# Stepper_driver.net
KiCad netlist of a schematic drawn in Altium Designer
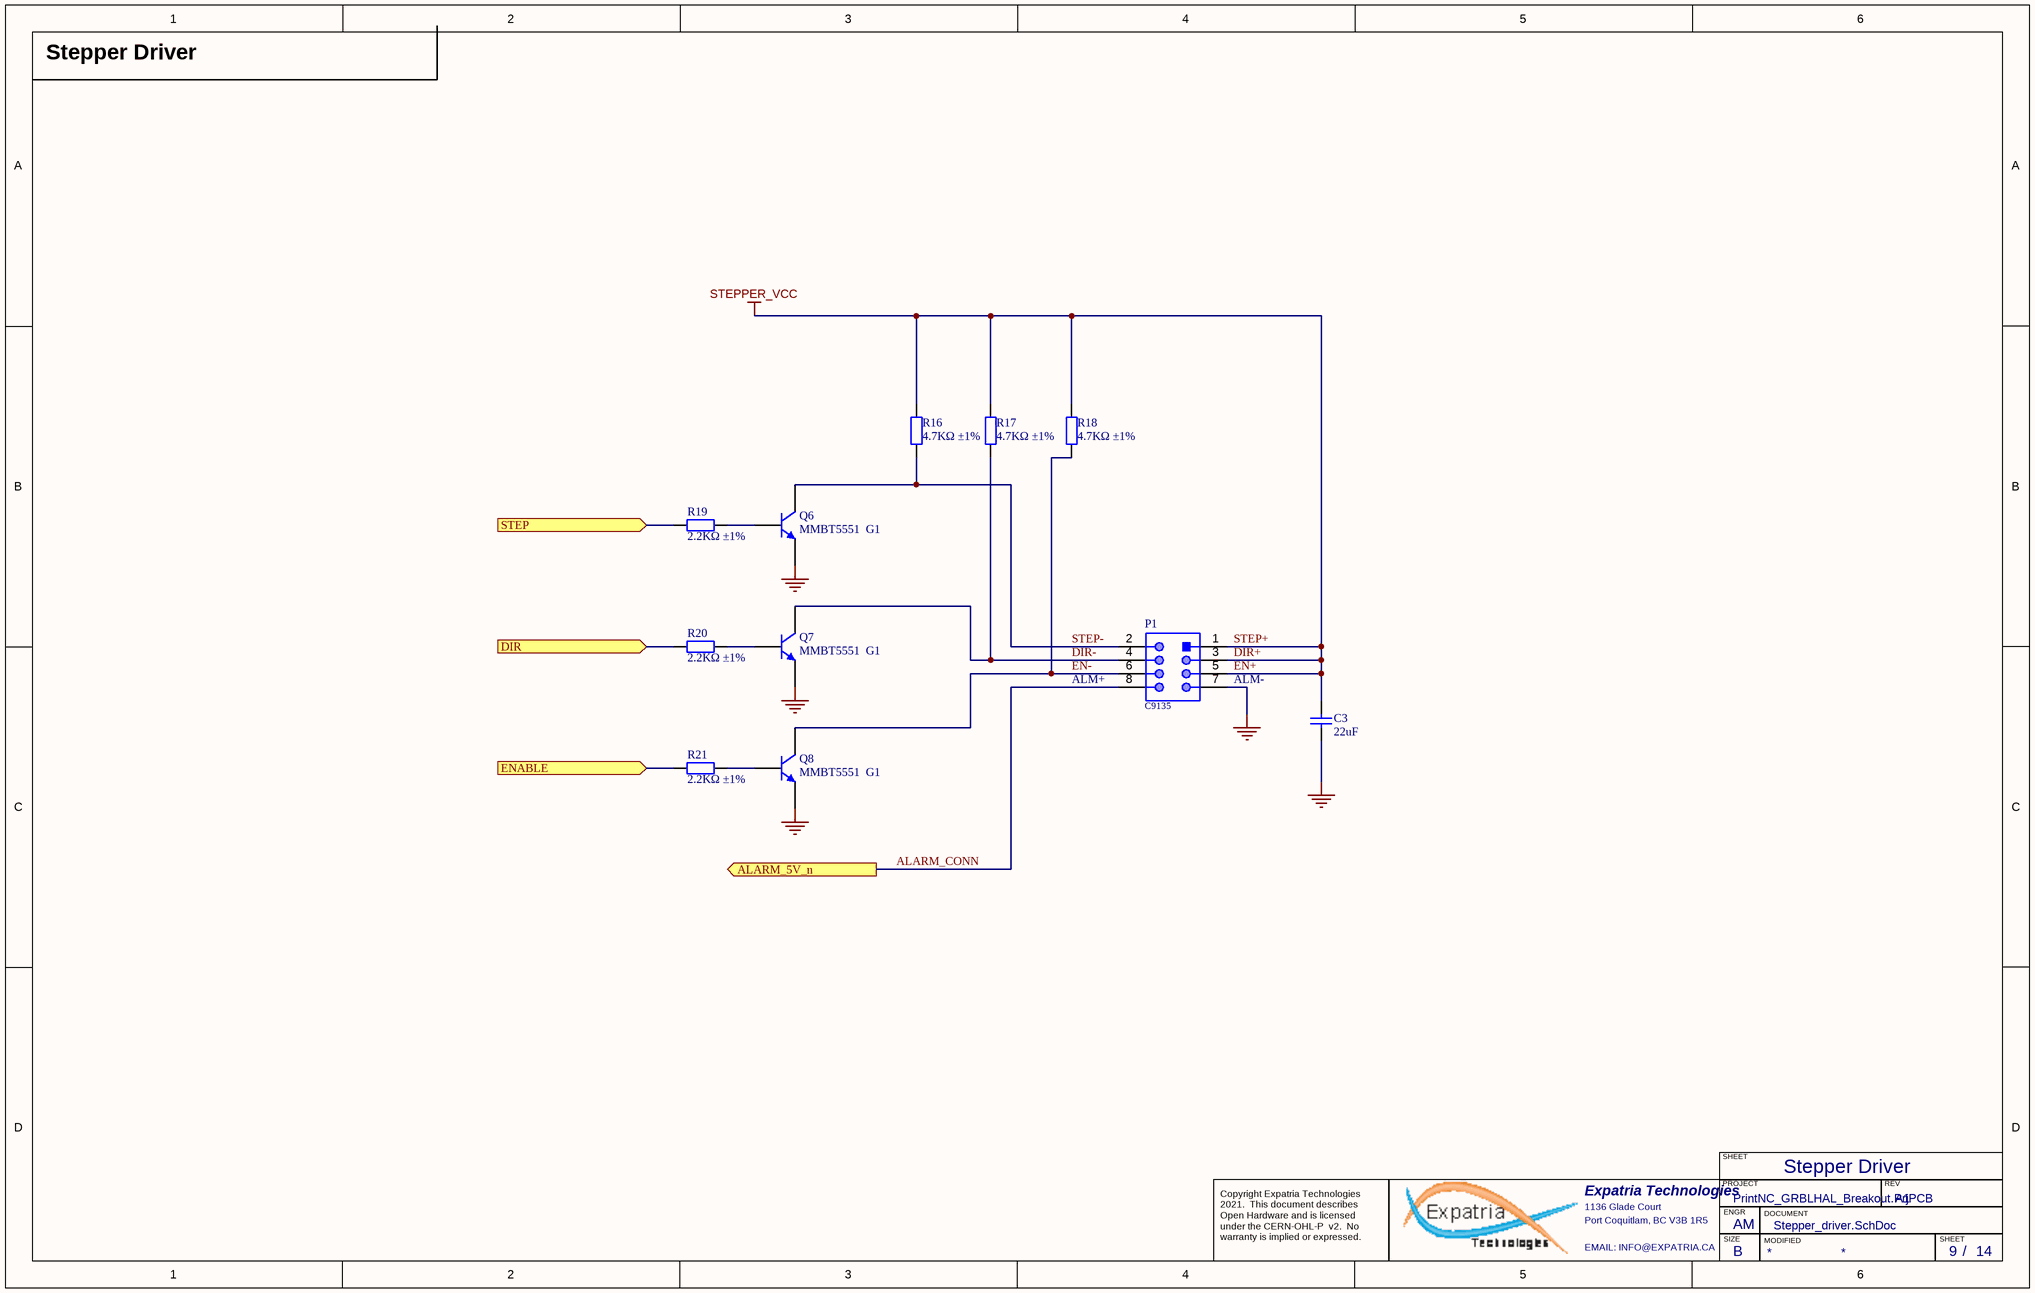
[diagram p0: Stepper_driver.SchDoc]

(export (version "E")
  (design (tool "Eeschema 10.0.6"))
  (components
    (comp (ref "C3")
      (value "22uF")
      (footprint "0805_C")
      (description "Chip capacitors")
      (fields
        (field (name "MANUFACTURER") "Samsung Electro-Mechanics")
        (field (name "PARTNUMBER") "CL21A226MAQNNNE")
      )
      (libsource (lib "Cap") (part "0805 22uF (226) 20% 25V"))
    )
    (comp (ref "P1")
      (value "C9135")
      (footprint "61200821621")
      (description "Male Box Header WR-BHD, THT, Vertical, pitch 2.54 mm, 8 pins")
      (fields (field (name "MANUFACTURER") "Wurth Elektronik") (field (name "PUBLISHER") "WurthElektronik"))
      (libsource (lib "PrintNC_GRBLHAL_Breakout") (part "WE-CN-2P-M-R8"))
    )
    (comp (ref "Q6")
      (value "MMBT5551  G1")
      (footprint "SOT-23(SOT-23-3)")
      (description "三极管")
      (libsource (lib "PrintNC_GRBLHAL_Breakout") (part "SOT-23 MMBT5551  G1"))
    )
    (comp (ref "Q7")
      (value "MMBT5551  G1")
      (footprint "SOT-23(SOT-23-3)")
      (description "三极管")
      (libsource (lib "PrintNC_GRBLHAL_Breakout") (part "SOT-23 MMBT5551  G1"))
    )
    (comp (ref "Q8")
      (value "MMBT5551  G1")
      (footprint "SOT-23(SOT-23-3)")
      (description "三极管")
      (libsource (lib "PrintNC_GRBLHAL_Breakout") (part "SOT-23 MMBT5551  G1"))
    )
    (comp (ref "R16")
      (value "4.7KΩ ±1%")
      (footprint "0402_R")
      (description "Chip resistor")
      (fields (field (name "MANUFACTURER") "Uniroyal Elec") (field (name "PARTNUMBER") "0402WGF4701TCE"))
      (libsource (lib "PrintNC_GRBLHAL_Breakout") (part "0402 4.7K (4701) 1%"))
    )
    (comp (ref "R17")
      (value "4.7KΩ ±1%")
      (footprint "0402_R")
      (description "Chip resistor")
      (fields (field (name "MANUFACTURER") "Uniroyal Elec") (field (name "PARTNUMBER") "0402WGF4701TCE"))
      (libsource (lib "PrintNC_GRBLHAL_Breakout") (part "0402 4.7K (4701) 1%"))
    )
    (comp (ref "R18")
      (value "4.7KΩ ±1%")
      (footprint "0402_R")
      (description "Chip resistor")
      (fields (field (name "MANUFACTURER") "Uniroyal Elec") (field (name "PARTNUMBER") "0402WGF4701TCE"))
      (libsource (lib "PrintNC_GRBLHAL_Breakout") (part "0402 4.7K (4701) 1%"))
    )
    (comp (ref "R19")
      (value "2.2KΩ ±1%")
      (footprint "0402_R")
      (description "Chip resistor")
      (fields (field (name "MANUFACTURER") "Uniroyal Elec") (field (name "PARTNUMBER") "0402WGF2201TCE"))
      (libsource (lib "PrintNC_GRBLHAL_Breakout") (part "0402 2.2K (2201) 1%"))
    )
    (comp (ref "R20")
      (value "2.2KΩ ±1%")
      (footprint "0402_R")
      (description "Chip resistor")
      (fields (field (name "MANUFACTURER") "Uniroyal Elec") (field (name "PARTNUMBER") "0402WGF2201TCE"))
      (libsource (lib "PrintNC_GRBLHAL_Breakout") (part "0402 2.2K (2201) 1%"))
    )
    (comp (ref "R21")
      (value "2.2KΩ ±1%")
      (footprint "0402_R")
      (description "Chip resistor")
      (fields (field (name "MANUFACTURER") "Uniroyal Elec") (field (name "PARTNUMBER") "0402WGF2201TCE"))
      (libsource (lib "PrintNC_GRBLHAL_Breakout") (part "0402 2.2K (2201) 1%"))
    )
  )
  (nets
    (net (code "1") (name "/ALARM_CONN") (class "Default")
      (node (ref "P1") (pin "8") (pinfunction "8_8") (pintype "passive"))
    )
    (net (code "2") (name "/DIR") (class "Default")
      (node (ref "R20") (pin "1") (pinfunction "1_1") (pintype "passive"))
    )
    (net (code "3") (name "/DIR-") (class "Default")
      (node (ref "P1") (pin "4") (pinfunction "4_4") (pintype "passive"))
      (node (ref "Q7") (pin "3") (pinfunction "C_3") (pintype "passive"))
      (node (ref "R17") (pin "1") (pinfunction "1_1") (pintype "passive"))
    )
    (net (code "4") (name "/EN-") (class "Default")
      (node (ref "P1") (pin "6") (pinfunction "6_6") (pintype "passive"))
      (node (ref "Q8") (pin "3") (pinfunction "C_3") (pintype "passive"))
      (node (ref "R18") (pin "1") (pinfunction "1_1") (pintype "passive"))
    )
    (net (code "5") (name "/ENABLE") (class "Default")
      (node (ref "R21") (pin "1") (pinfunction "1_1") (pintype "passive"))
    )
    (net (code "6") (name "/STEP") (class "Default")
      (node (ref "R19") (pin "1") (pinfunction "1_1") (pintype "passive"))
    )
    (net (code "7") (name "/STEP-") (class "Default")
      (node (ref "P1") (pin "2") (pinfunction "2_2") (pintype "passive"))
      (node (ref "Q6") (pin "3") (pinfunction "C_3") (pintype "passive"))
      (node (ref "R16") (pin "1") (pinfunction "1_1") (pintype "passive"))
    )
    (net (code "8") (name "GND") (class "Default")
      (node (ref "C3") (pin "1") (pinfunction "1_1") (pintype "passive"))
      (node (ref "P1") (pin "7") (pinfunction "7_7") (pintype "passive"))
      (node (ref "Q6") (pin "2") (pinfunction "E_2") (pintype "passive"))
      (node (ref "Q7") (pin "2") (pinfunction "E_2") (pintype "passive"))
      (node (ref "Q8") (pin "2") (pinfunction "E_2") (pintype "passive"))
    )
    (net (code "9") (name "Net-(Q6-B)") (class "Default")
      (node (ref "Q6") (pin "1") (pinfunction "B_1") (pintype "passive"))
      (node (ref "R19") (pin "2") (pinfunction "2_2") (pintype "passive"))
    )
    (net (code "10") (name "Net-(Q7-B)") (class "Default")
      (node (ref "Q7") (pin "1") (pinfunction "B_1") (pintype "passive"))
      (node (ref "R20") (pin "2") (pinfunction "2_2") (pintype "passive"))
    )
    (net (code "11") (name "Net-(Q8-B)") (class "Default")
      (node (ref "Q8") (pin "1") (pinfunction "B_1") (pintype "passive"))
      (node (ref "R21") (pin "2") (pinfunction "2_2") (pintype "passive"))
    )
    (net (code "12") (name "STEPPER_VCC") (class "Default")
      (node (ref "C3") (pin "2") (pinfunction "2_2") (pintype "passive"))
      (node (ref "P1") (pin "1") (pinfunction "1_1") (pintype "passive"))
      (node (ref "P1") (pin "3") (pinfunction "3_3") (pintype "passive"))
      (node (ref "P1") (pin "5") (pinfunction "5_5") (pintype "passive"))
      (node (ref "R16") (pin "2") (pinfunction "2_2") (pintype "passive"))
      (node (ref "R17") (pin "2") (pinfunction "2_2") (pintype "passive"))
      (node (ref "R18") (pin "2") (pinfunction "2_2") (pintype "passive"))
    )
  )
)
